# -LTC3406.net
KiCad netlist of a schematic drawn in Altium Designer
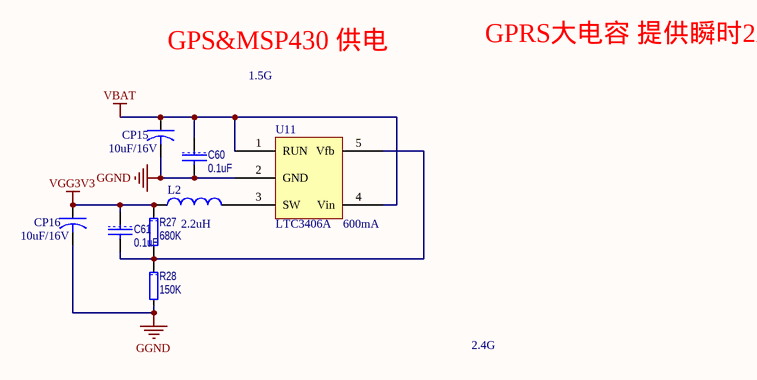
[diagram p0: -LTC3406_电源.SchDoc]

(export (version "E")
  (design (tool "Eeschema 10.0.6"))
  (components
    (comp (ref "C60")
      (value "0.1uF")
      (footprint "1608[0603]")
      (description "Capacitor")
      (fields (field (name "MANUFACTURER") "TDK"))
      (libsource (lib "*") (part "CAP"))
    )
    (comp (ref "C61")
      (value "0.1uF")
      (footprint "1608[0603]")
      (description "Capacitor")
      (fields (field (name "MANUFACTURER") "TDK"))
      (libsource (lib "*") (part "CAP"))
    )
    (comp (ref "CP15")
      (value "10uF/16V")
      (footprint "3216[1206]")
      (description "Tantalum Capacitor")
      (libsource (lib "*") (part "CAPACITOR"))
    )
    (comp (ref "CP16")
      (value "10uF/16V")
      (footprint "3216[1206]")
      (description "Tantalum Capacitor")
      (libsource (lib "*") (part "CAPACITOR"))
    )
    (comp (ref "L2")
      (value "2.2uH")
      (footprint "INDP3232")
      (description "Inductor")
      (fields (field (name "Comment") "CDRH2D18/HP 2R2") (field (name "PUBLISHER") "Altium Limited"))
      (libsource (lib "Miscellaneous Devices") (part "Inductor"))
    )
    (comp (ref "R27")
      (value "680K")
      (footprint "0603R")
      (description "RES")
      (fields (field (name "MANUFACTURER") "vishay"))
      (libsource (lib "*") (part "RES"))
    )
    (comp (ref "R28")
      (value "150K")
      (footprint "0603R")
      (description "RES")
      (fields (field (name "MANUFACTURER") "vishay"))
      (libsource (lib "*") (part "RES"))
    )
    (comp (ref "U11")
      (value "LTC3406A")
      (footprint "SOT23-5AN")
      (description "POWER")
      (libsource (lib "S3C2440V8") (part "LTC3406A"))
    )
  )
  (nets
    (net (code "1") (name "GGND") (class "Default")
      (node (ref "C60") (pin "2") (pinfunction "2_2") (pintype "passive"))
      (node (ref "CP15") (pin "2") (pinfunction "2_2") (pintype "passive"))
      (node (ref "CP16") (pin "2") (pinfunction "2_2") (pintype "passive"))
      (node (ref "R28") (pin "2") (pinfunction "2_2") (pintype "passive"))
      (node (ref "U11") (pin "2") (pinfunction "GND_2") (pintype "passive"))
    )
    (net (code "2") (name "Net-(U11-SW)") (class "Default")
      (node (ref "L2") (pin "2") (pinfunction "2_2") (pintype "passive"))
      (node (ref "U11") (pin "3") (pinfunction "SW_3") (pintype "passive"))
    )
    (net (code "3") (name "Net-(U11-Vfb)") (class "Default")
      (node (ref "C61") (pin "2") (pinfunction "2_2") (pintype "passive"))
      (node (ref "R27") (pin "2") (pinfunction "2_2") (pintype "passive"))
      (node (ref "R28") (pin "1") (pinfunction "1_1") (pintype "passive"))
      (node (ref "U11") (pin "5") (pinfunction "Vfb_5") (pintype "passive"))
    )
    (net (code "4") (name "VBAT") (class "Default")
      (node (ref "C60") (pin "1") (pinfunction "1_1") (pintype "passive"))
      (node (ref "CP15") (pin "1") (pinfunction "1_1") (pintype "passive"))
      (node (ref "U11") (pin "1") (pinfunction "RUN_1") (pintype "passive"))
      (node (ref "U11") (pin "4") (pinfunction "Vin_4") (pintype "passive"))
    )
    (net (code "5") (name "VGG3V3") (class "Default")
      (node (ref "C61") (pin "1") (pinfunction "1_1") (pintype "passive"))
      (node (ref "CP16") (pin "1") (pinfunction "1_1") (pintype "passive"))
      (node (ref "L2") (pin "1") (pinfunction "1_1") (pintype "passive"))
      (node (ref "R27") (pin "1") (pinfunction "1_1") (pintype "passive"))
    )
  )
)
